# M2_Breakin.net
KiCad netlist of a schematic drawn in Altium Designer
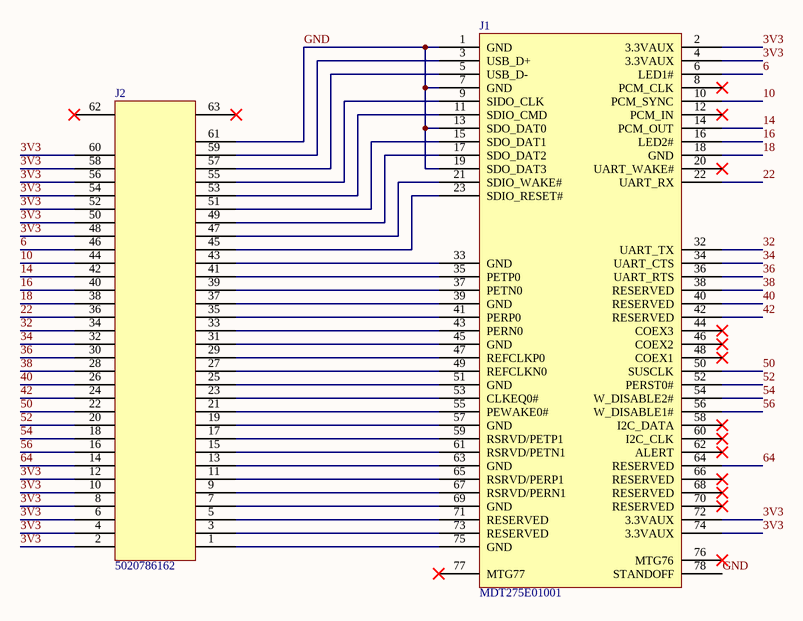
[diagram p0: M2 Breakin.SchDoc]

(export (version "E")
  (design (tool "Eeschema 10.0.6"))
  (components
    (comp (ref "J1")
      (value "MDT275E01001")
      (footprint "MDT275E01001")
      (description "CONN M.2 E FMALE 67POS 0.020 GOLD")
      (libsource (lib "KBuchka-IntLib") (part "MDT275E01001"))
    )
    (comp (ref "J2")
      (value "5020786162")
      (footprint "5020786162")
      (description "Conn FPC Connector SKT 61 POS 0.25mm Solder RA SMD T/R")
      (libsource (lib "KBuchka-IntLib") (part "5020786162"))
    )
  )
  (nets
    (net (code "1") (name "/3V3") (class "Default")
      (node (ref "J1") (pin "2") (pinfunction "3.3VAUX_2") (pintype "passive"))
      (node (ref "J1") (pin "4") (pinfunction "3.3VAUX_4") (pintype "passive"))
      (node (ref "J1") (pin "72") (pinfunction "3.3VAUX_72") (pintype "passive"))
      (node (ref "J1") (pin "74") (pinfunction "3.3VAUX_74") (pintype "passive"))
      (node (ref "J2") (pin "10") (pintype "passive"))
      (node (ref "J2") (pin "12") (pintype "passive"))
      (node (ref "J2") (pin "2") (pintype "passive"))
      (node (ref "J2") (pin "4") (pintype "passive"))
      (node (ref "J2") (pin "48") (pintype "passive"))
      (node (ref "J2") (pin "50") (pintype "passive"))
      (node (ref "J2") (pin "52") (pintype "passive"))
      (node (ref "J2") (pin "54") (pintype "passive"))
      (node (ref "J2") (pin "56") (pintype "passive"))
      (node (ref "J2") (pin "58") (pintype "passive"))
      (node (ref "J2") (pin "6") (pintype "passive"))
      (node (ref "J2") (pin "60") (pintype "passive"))
      (node (ref "J2") (pin "8") (pintype "passive"))
    )
    (net (code "2") (name "/6") (class "Default")
      (node (ref "J1") (pin "6") (pinfunction "LED1#_6") (pintype "passive"))
      (node (ref "J2") (pin "46") (pintype "passive"))
    )
    (net (code "3") (name "/10") (class "Default")
      (node (ref "J1") (pin "10") (pinfunction "PCM_SYNC_10") (pintype "passive"))
      (node (ref "J2") (pin "44") (pintype "passive"))
    )
    (net (code "4") (name "/14") (class "Default")
      (node (ref "J1") (pin "14") (pinfunction "PCM_OUT_14") (pintype "passive"))
      (node (ref "J2") (pin "42") (pintype "passive"))
    )
    (net (code "5") (name "/16") (class "Default")
      (node (ref "J1") (pin "16") (pinfunction "LED2#_16") (pintype "passive"))
      (node (ref "J2") (pin "40") (pintype "passive"))
    )
    (net (code "6") (name "/18") (class "Default")
      (node (ref "J1") (pin "18") (pinfunction "GND_18") (pintype "passive"))
      (node (ref "J2") (pin "38") (pintype "passive"))
    )
    (net (code "7") (name "/22") (class "Default")
      (node (ref "J1") (pin "22") (pinfunction "UART_RX_22") (pintype "passive"))
      (node (ref "J2") (pin "36") (pintype "passive"))
    )
    (net (code "8") (name "/32") (class "Default")
      (node (ref "J1") (pin "32") (pinfunction "UART_TX_32") (pintype "passive"))
      (node (ref "J2") (pin "34") (pintype "passive"))
    )
    (net (code "9") (name "/34") (class "Default")
      (node (ref "J1") (pin "34") (pinfunction "UART_CTS_34") (pintype "passive"))
      (node (ref "J2") (pin "32") (pintype "passive"))
    )
    (net (code "10") (name "/36") (class "Default")
      (node (ref "J1") (pin "36") (pinfunction "UART_RTS_36") (pintype "passive"))
      (node (ref "J2") (pin "30") (pintype "passive"))
    )
    (net (code "11") (name "/38") (class "Default")
      (node (ref "J1") (pin "38") (pinfunction "RESERVED_38") (pintype "passive"))
      (node (ref "J2") (pin "28") (pintype "passive"))
    )
    (net (code "12") (name "/40") (class "Default")
      (node (ref "J1") (pin "40") (pinfunction "RESERVED_40") (pintype "passive"))
      (node (ref "J2") (pin "26") (pintype "passive"))
    )
    (net (code "13") (name "/42") (class "Default")
      (node (ref "J1") (pin "42") (pinfunction "RESERVED_42") (pintype "passive"))
      (node (ref "J2") (pin "24") (pintype "passive"))
    )
    (net (code "14") (name "/50") (class "Default")
      (node (ref "J1") (pin "50") (pinfunction "SUSCLK_50") (pintype "passive"))
      (node (ref "J2") (pin "22") (pintype "passive"))
    )
    (net (code "15") (name "/52") (class "Default")
      (node (ref "J1") (pin "52") (pinfunction "PERST0#_52") (pintype "passive"))
      (node (ref "J2") (pin "20") (pintype "passive"))
    )
    (net (code "16") (name "/54") (class "Default")
      (node (ref "J1") (pin "54") (pinfunction "W_DISABLE2#_54") (pintype "passive"))
      (node (ref "J2") (pin "18") (pintype "passive"))
    )
    (net (code "17") (name "/56") (class "Default")
      (node (ref "J1") (pin "56") (pinfunction "W_DISABLE1#_56") (pintype "passive"))
      (node (ref "J2") (pin "16") (pintype "passive"))
    )
    (net (code "18") (name "/64") (class "Default")
      (node (ref "J1") (pin "64") (pinfunction "RESERVED_64") (pintype "passive"))
      (node (ref "J2") (pin "14") (pintype "passive"))
    )
    (net (code "19") (name "/GND") (class "Default")
      (node (ref "J1") (pin "1") (pinfunction "GND_1") (pintype "passive"))
      (node (ref "J1") (pin "13") (pinfunction "SDO_DAT0_13") (pintype "passive"))
      (node (ref "J1") (pin "19") (pinfunction "SDO_DAT3_19") (pintype "passive"))
      (node (ref "J1") (pin "7") (pinfunction "GND_7") (pintype "passive"))
      (node (ref "J1") (pin "78") (pinfunction "STANDOFF_78") (pintype "passive"))
      (node (ref "J2") (pin "61") (pintype "passive"))
    )
    (net (code "20") (name "Net-(J1-CLKEQ0#)") (class "Default")
      (node (ref "J1") (pin "53") (pinfunction "CLKEQ0#_53") (pintype "passive"))
      (node (ref "J2") (pin "23") (pintype "passive"))
    )
    (net (code "21") (name "Net-(J1-GND-Pad33)") (class "Default")
      (node (ref "J1") (pin "33") (pinfunction "GND_33") (pintype "passive"))
      (node (ref "J2") (pin "43") (pintype "passive"))
    )
    (net (code "22") (name "Net-(J1-GND-Pad39)") (class "Default")
      (node (ref "J1") (pin "39") (pinfunction "GND_39") (pintype "passive"))
      (node (ref "J2") (pin "37") (pintype "passive"))
    )
    (net (code "23") (name "Net-(J1-GND-Pad45)") (class "Default")
      (node (ref "J1") (pin "45") (pinfunction "GND_45") (pintype "passive"))
      (node (ref "J2") (pin "31") (pintype "passive"))
    )
    (net (code "24") (name "Net-(J1-GND-Pad51)") (class "Default")
      (node (ref "J1") (pin "51") (pinfunction "GND_51") (pintype "passive"))
      (node (ref "J2") (pin "25") (pintype "passive"))
    )
    (net (code "25") (name "Net-(J1-GND-Pad57)") (class "Default")
      (node (ref "J1") (pin "57") (pinfunction "GND_57") (pintype "passive"))
      (node (ref "J2") (pin "19") (pintype "passive"))
    )
    (net (code "26") (name "Net-(J1-GND-Pad63)") (class "Default")
      (node (ref "J1") (pin "63") (pinfunction "GND_63") (pintype "passive"))
      (node (ref "J2") (pin "13") (pintype "passive"))
    )
    (net (code "27") (name "Net-(J1-GND-Pad69)") (class "Default")
      (node (ref "J1") (pin "69") (pinfunction "GND_69") (pintype "passive"))
      (node (ref "J2") (pin "7") (pintype "passive"))
    )
    (net (code "28") (name "Net-(J1-GND-Pad75)") (class "Default")
      (node (ref "J1") (pin "75") (pinfunction "GND_75") (pintype "passive"))
      (node (ref "J2") (pin "1") (pintype "passive"))
    )
    (net (code "29") (name "Net-(J1-PERN0)") (class "Default")
      (node (ref "J1") (pin "43") (pinfunction "PERN0_43") (pintype "passive"))
      (node (ref "J2") (pin "33") (pintype "passive"))
    )
    (net (code "30") (name "Net-(J1-PERP0)") (class "Default")
      (node (ref "J1") (pin "41") (pinfunction "PERP0_41") (pintype "passive"))
      (node (ref "J2") (pin "35") (pintype "passive"))
    )
    (net (code "31") (name "Net-(J1-PETN0)") (class "Default")
      (node (ref "J1") (pin "37") (pinfunction "PETN0_37") (pintype "passive"))
      (node (ref "J2") (pin "39") (pintype "passive"))
    )
    (net (code "32") (name "Net-(J1-PETP0)") (class "Default")
      (node (ref "J1") (pin "35") (pinfunction "PETP0_35") (pintype "passive"))
      (node (ref "J2") (pin "41") (pintype "passive"))
    )
    (net (code "33") (name "Net-(J1-PEWAKE0#)") (class "Default")
      (node (ref "J1") (pin "55") (pinfunction "PEWAKE0#_55") (pintype "passive"))
      (node (ref "J2") (pin "21") (pintype "passive"))
    )
    (net (code "34") (name "Net-(J1-REFCLKN0)") (class "Default")
      (node (ref "J1") (pin "49") (pinfunction "REFCLKN0_49") (pintype "passive"))
      (node (ref "J2") (pin "27") (pintype "passive"))
    )
    (net (code "35") (name "Net-(J1-REFCLKP0)") (class "Default")
      (node (ref "J1") (pin "47") (pinfunction "REFCLKP0_47") (pintype "passive"))
      (node (ref "J2") (pin "29") (pintype "passive"))
    )
    (net (code "36") (name "Net-(J1-RESERVED-Pad71)") (class "Default")
      (node (ref "J1") (pin "71") (pinfunction "RESERVED_71") (pintype "passive"))
      (node (ref "J2") (pin "5") (pintype "passive"))
    )
    (net (code "37") (name "Net-(J1-RESERVED-Pad73)") (class "Default")
      (node (ref "J1") (pin "73") (pinfunction "RESERVED_73") (pintype "passive"))
      (node (ref "J2") (pin "3") (pintype "passive"))
    )
    (net (code "38") (name "Net-(J1-RSRVD{slash}PERN1)") (class "Default")
      (node (ref "J1") (pin "67") (pinfunction "RSRVD/PERN1_67") (pintype "passive"))
      (node (ref "J2") (pin "9") (pintype "passive"))
    )
    (net (code "39") (name "Net-(J1-RSRVD{slash}PERP1)") (class "Default")
      (node (ref "J1") (pin "65") (pinfunction "RSRVD/PERP1_65") (pintype "passive"))
      (node (ref "J2") (pin "11") (pintype "passive"))
    )
    (net (code "40") (name "Net-(J1-RSRVD{slash}PETN1)") (class "Default")
      (node (ref "J1") (pin "61") (pinfunction "RSRVD/PETN1_61") (pintype "passive"))
      (node (ref "J2") (pin "15") (pintype "passive"))
    )
    (net (code "41") (name "Net-(J1-RSRVD{slash}PETP1)") (class "Default")
      (node (ref "J1") (pin "59") (pinfunction "RSRVD/PETP1_59") (pintype "passive"))
      (node (ref "J2") (pin "17") (pintype "passive"))
    )
    (net (code "42") (name "Net-(J1-SDIO_CMD)") (class "Default")
      (node (ref "J1") (pin "11") (pinfunction "SDIO_CMD_11") (pintype "passive"))
      (node (ref "J2") (pin "53") (pintype "passive"))
    )
    (net (code "43") (name "Net-(J1-SDIO_RESET#)") (class "Default")
      (node (ref "J1") (pin "23") (pinfunction "SDIO_RESET#_23") (pintype "passive"))
      (node (ref "J2") (pin "45") (pintype "passive"))
    )
    (net (code "44") (name "Net-(J1-SDIO_WAKE#)") (class "Default")
      (node (ref "J1") (pin "21") (pinfunction "SDIO_WAKE#_21") (pintype "passive"))
      (node (ref "J2") (pin "47") (pintype "passive"))
    )
    (net (code "45") (name "Net-(J1-SDO_DAT1)") (class "Default")
      (node (ref "J1") (pin "15") (pinfunction "SDO_DAT1_15") (pintype "passive"))
      (node (ref "J2") (pin "51") (pintype "passive"))
    )
    (net (code "46") (name "Net-(J1-SDO_DAT2)") (class "Default")
      (node (ref "J1") (pin "17") (pinfunction "SDO_DAT2_17") (pintype "passive"))
      (node (ref "J2") (pin "49") (pintype "passive"))
    )
    (net (code "47") (name "Net-(J1-SIDO_CLK)") (class "Default")
      (node (ref "J1") (pin "9") (pinfunction "SIDO_CLK_9") (pintype "passive"))
      (node (ref "J2") (pin "55") (pintype "passive"))
    )
    (net (code "48") (name "Net-(J1-USB_D+)") (class "Default")
      (node (ref "J1") (pin "3") (pinfunction "USB_D+_3") (pintype "passive"))
      (node (ref "J2") (pin "59") (pintype "passive"))
    )
    (net (code "49") (name "Net-(J1-USB_D-)") (class "Default")
      (node (ref "J1") (pin "5") (pinfunction "USB_D-_5") (pintype "passive"))
      (node (ref "J2") (pin "57") (pintype "passive"))
    )
    (net (code "50") (name "unconnected-(J1-ALERT-Pad62)") (class "Default")
      (node (ref "J1") (pin "62") (pinfunction "ALERT_62") (pintype "passive+no_connect"))
    )
    (net (code "51") (name "unconnected-(J1-COEX1-Pad48)") (class "Default")
      (node (ref "J1") (pin "48") (pinfunction "COEX1_48") (pintype "passive+no_connect"))
    )
    (net (code "52") (name "unconnected-(J1-COEX2-Pad46)") (class "Default")
      (node (ref "J1") (pin "46") (pinfunction "COEX2_46") (pintype "passive+no_connect"))
    )
    (net (code "53") (name "unconnected-(J1-COEX3-Pad44)") (class "Default")
      (node (ref "J1") (pin "44") (pinfunction "COEX3_44") (pintype "passive+no_connect"))
    )
    (net (code "54") (name "unconnected-(J1-I2C_CLK-Pad60)") (class "Default")
      (node (ref "J1") (pin "60") (pinfunction "I2C_CLK_60") (pintype "passive+no_connect"))
    )
    (net (code "55") (name "unconnected-(J1-I2C_DATA-Pad58)") (class "Default")
      (node (ref "J1") (pin "58") (pinfunction "I2C_DATA_58") (pintype "passive+no_connect"))
    )
    (net (code "56") (name "unconnected-(J1-MTG76-Pad76)") (class "Default")
      (node (ref "J1") (pin "76") (pinfunction "MTG76_76") (pintype "passive+no_connect"))
    )
    (net (code "57") (name "unconnected-(J1-MTG77-Pad77)") (class "Default")
      (node (ref "J1") (pin "77") (pinfunction "MTG77_77") (pintype "passive+no_connect"))
    )
    (net (code "58") (name "unconnected-(J1-PCM_CLK-Pad8)") (class "Default")
      (node (ref "J1") (pin "8") (pinfunction "PCM_CLK_8") (pintype "passive+no_connect"))
    )
    (net (code "59") (name "unconnected-(J1-PCM_IN-Pad12)") (class "Default")
      (node (ref "J1") (pin "12") (pinfunction "PCM_IN_12") (pintype "passive+no_connect"))
    )
    (net (code "60") (name "unconnected-(J1-RESERVED-Pad66)") (class "Default")
      (node (ref "J1") (pin "66") (pinfunction "RESERVED_66") (pintype "passive+no_connect"))
    )
    (net (code "61") (name "unconnected-(J1-RESERVED-Pad68)") (class "Default")
      (node (ref "J1") (pin "68") (pinfunction "RESERVED_68") (pintype "passive+no_connect"))
    )
    (net (code "62") (name "unconnected-(J1-RESERVED-Pad70)") (class "Default")
      (node (ref "J1") (pin "70") (pinfunction "RESERVED_70") (pintype "passive+no_connect"))
    )
    (net (code "63") (name "unconnected-(J1-UART_WAKE#-Pad20)") (class "Default")
      (node (ref "J1") (pin "20") (pinfunction "UART_WAKE#_20") (pintype "passive+no_connect"))
    )
    (net (code "64") (name "unconnected-(J2-Pad62)") (class "Default")
      (node (ref "J2") (pin "62") (pintype "passive+no_connect"))
    )
    (net (code "65") (name "unconnected-(J2-Pad63)") (class "Default")
      (node (ref "J2") (pin "63") (pintype "passive+no_connect"))
    )
  )
)
